# MAU1.net
KiCad netlist of a schematic drawn in EAGLE
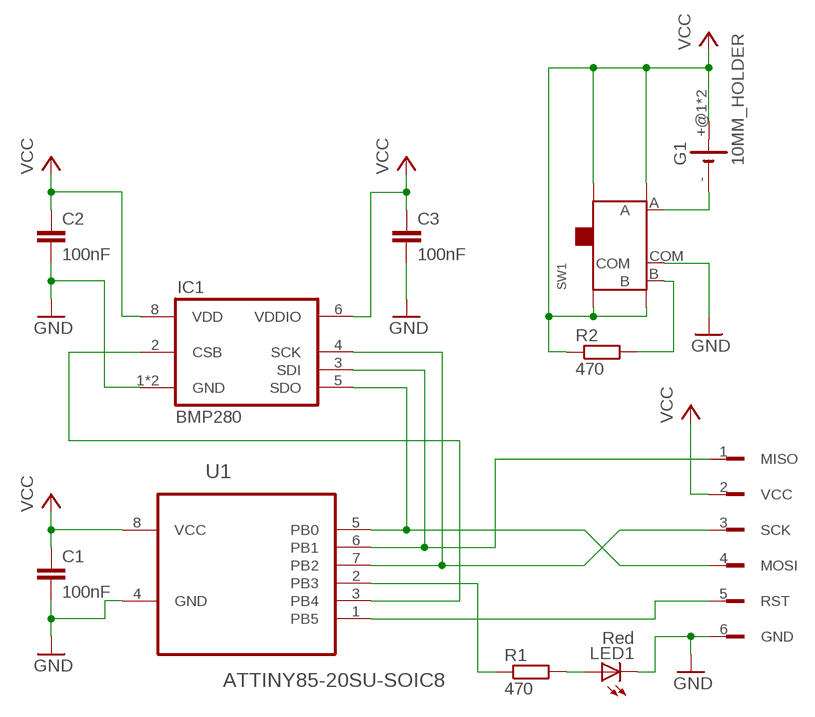
[diagram p0: schematic, sheet 1]

(export (version "E")
  (design (tool "Eeschema 10.0.6"))
  (components
    (comp (ref "C1")
      (value "100nF")
      (footprint "eagle-import:C0603K")
      (libsource (lib "eagle-import") (part "C-EUC0603K"))
    )
    (comp (ref "C2")
      (value "100nF")
      (footprint "eagle-import:C0603K")
      (libsource (lib "eagle-import") (part "C-EUC0603K"))
    )
    (comp (ref "C3")
      (value "100nF")
      (footprint "eagle-import:C0603K")
      (libsource (lib "eagle-import") (part "C-EUC0603K"))
    )
    (comp (ref "G1")
      (value "10MM_HOLDER")
      (footprint "eagle-import:10MM_HOLDER")
      (libsource (lib "eagle-import") (part "10MM_HOLDER"))
    )
    (comp (ref "IC1")
      (value "BMP280")
      (footprint "eagle-import:BMP280")
      (libsource (lib "eagle-import") (part "BMP280"))
    )
    (comp (ref "LED1")
      (value "Red")
      (footprint "eagle-import:KA-3528ASYC")
      (libsource (lib "eagle-import") (part "LEDKA-3528ASYC"))
    )
    (comp (ref "R1")
      (value "470")
      (footprint "eagle-import:R0603")
      (libsource (lib "eagle-import") (part "R-EU_R0603"))
    )
    (comp (ref "R2")
      (value "470")
      (footprint "eagle-import:R0603")
      (libsource (lib "eagle-import") (part "R-EU_R0603"))
    )
    (comp (ref "SW1")
      (value "SMD-TOGGLE-SWITCH-ON-ON(3+4P-6.7X2.7MM)SLIDE_LATERAL")
      (footprint "eagle-import:SW7-SMD-6.7X2.6X1.4MM-90D")
      (libsource (lib "eagle-import") (part "SMD-TOGGLE-SWITCH-ON-ON(3+4P-6.7X2.7MM)SLIDE_LATERAL"))
    )
    (comp (ref "U$1")
      (value "ISP_CONN_6_FDRILL16")
      (footprint "eagle-import:ISP_CONN_6_F_DRILL16")
      (libsource (lib "eagle-import") (part "ISP_CONN_6_FDRILL16"))
    )
    (comp (ref "U1")
      (value "ATTINY85-20SU-SOIC8")
      (footprint "eagle-import:SOIC8-1.27-5.3X5.3MM")
      (fields (field (name "MPN") "ATTINY85-20SU"))
      (libsource (lib "eagle-import") (part "MCU-ATTINY85-20SU(SOIC8)"))
    )
  )
  (nets
    (net (code "1") (name "GND") (class "Default")
      (node (ref "C1") (pin "2") (pinfunction "2_2") (pintype "passive"))
      (node (ref "C2") (pin "2") (pinfunction "2_2") (pintype "passive"))
      (node (ref "C3") (pin "2") (pinfunction "2_2") (pintype "passive"))
      (node (ref "IC1") (pin "1") (pinfunction "GND_1") (pintype "power_in"))
      (node (ref "IC1") (pin "7") (pinfunction "GND_7") (pintype "power_in"))
      (node (ref "LED1") (pin "C") (pinfunction "C_C") (pintype "passive"))
      (node (ref "SW1") (pin "COM") (pinfunction "COM_COM") (pintype "bidirectional"))
      (node (ref "U$1") (pin "6") (pinfunction "GND_6") (pintype "bidirectional"))
      (node (ref "U1") (pin "4") (pinfunction "GND_4") (pintype "passive"))
    )
    (net (code "2") (name "Net-(G1-Pad-)") (class "Default")
      (node (ref "G1") (pin "-") (pinfunction "-_-") (pintype "passive"))
      (node (ref "SW1") (pin "A") (pinfunction "A_A") (pintype "bidirectional"))
    )
    (net (code "3") (name "Net-(IC1-CSB)") (class "Default")
      (node (ref "IC1") (pin "2") (pinfunction "CSB_2") (pintype "input"))
      (node (ref "U1") (pin "3") (pinfunction "PB4_3") (pintype "bidirectional"))
    )
    (net (code "4") (name "Net-(IC1-SCK)") (class "Default")
      (node (ref "IC1") (pin "4") (pinfunction "SCK_4") (pintype "bidirectional"))
      (node (ref "U$1") (pin "3") (pinfunction "SCK_3") (pintype "bidirectional"))
      (node (ref "U1") (pin "7") (pinfunction "PB2_7") (pintype "bidirectional"))
    )
    (net (code "5") (name "Net-(IC1-SDI)") (class "Default")
      (node (ref "IC1") (pin "3") (pinfunction "SDI_3") (pintype "bidirectional"))
      (node (ref "U$1") (pin "1") (pinfunction "MISO_1") (pintype "bidirectional"))
      (node (ref "U1") (pin "6") (pinfunction "PB1_6") (pintype "bidirectional"))
    )
    (net (code "6") (name "Net-(IC1-SDO)") (class "Default")
      (node (ref "IC1") (pin "5") (pinfunction "SDO_5") (pintype "input"))
      (node (ref "U$1") (pin "4") (pinfunction "MOSI_4") (pintype "bidirectional"))
      (node (ref "U1") (pin "5") (pinfunction "PB0_5") (pintype "bidirectional"))
    )
    (net (code "7") (name "Net-(LED1-PadA)") (class "Default")
      (node (ref "LED1") (pin "A") (pinfunction "A_A") (pintype "passive"))
      (node (ref "R1") (pin "2") (pinfunction "2_2") (pintype "passive"))
    )
    (net (code "8") (name "Net-(R2-Pad2)") (class "Default")
      (node (ref "R2") (pin "2") (pinfunction "2_2") (pintype "passive"))
      (node (ref "SW1") (pin "B") (pinfunction "B_B") (pintype "bidirectional"))
    )
    (net (code "9") (name "Net-(U$1-RST)") (class "Default")
      (node (ref "U$1") (pin "5") (pinfunction "RST_5") (pintype "bidirectional"))
      (node (ref "U1") (pin "1") (pinfunction "PB5_1") (pintype "bidirectional"))
    )
    (net (code "10") (name "Net-(U1-PB3)") (class "Default")
      (node (ref "R1") (pin "1") (pinfunction "1_1") (pintype "passive"))
      (node (ref "U1") (pin "2") (pinfunction "PB3_2") (pintype "bidirectional"))
    )
    (net (code "11") (name "VCC") (class "Default")
      (node (ref "C1") (pin "1") (pinfunction "1_1") (pintype "passive"))
      (node (ref "C2") (pin "1") (pinfunction "1_1") (pintype "passive"))
      (node (ref "C3") (pin "1") (pinfunction "1_1") (pintype "passive"))
      (node (ref "G1") (pin "+@1") (pinfunction "+_+@1") (pintype "passive"))
      (node (ref "G1") (pin "+@2") (pinfunction "+_+@2") (pintype "passive"))
      (node (ref "IC1") (pin "6") (pinfunction "VDDIO_6") (pintype "power_in"))
      (node (ref "IC1") (pin "8") (pinfunction "VDD_8") (pintype "power_in"))
      (node (ref "R2") (pin "1") (pinfunction "1_1") (pintype "passive"))
      (node (ref "SW1") (pin "P1") (pinfunction "SS4_P1") (pintype "bidirectional"))
      (node (ref "SW1") (pin "P2") (pinfunction "SS3_P2") (pintype "bidirectional"))
      (node (ref "SW1") (pin "P3") (pinfunction "SS2_P3") (pintype "bidirectional"))
      (node (ref "SW1") (pin "P4") (pinfunction "SS1_P4") (pintype "bidirectional"))
      (node (ref "U$1") (pin "2") (pinfunction "VCC_2") (pintype "bidirectional"))
      (node (ref "U1") (pin "8") (pinfunction "VCC_8") (pintype "power_in"))
    )
  )
)
